# trs80_m2.net
KiCad netlist of a schematic drawn in EAGLE
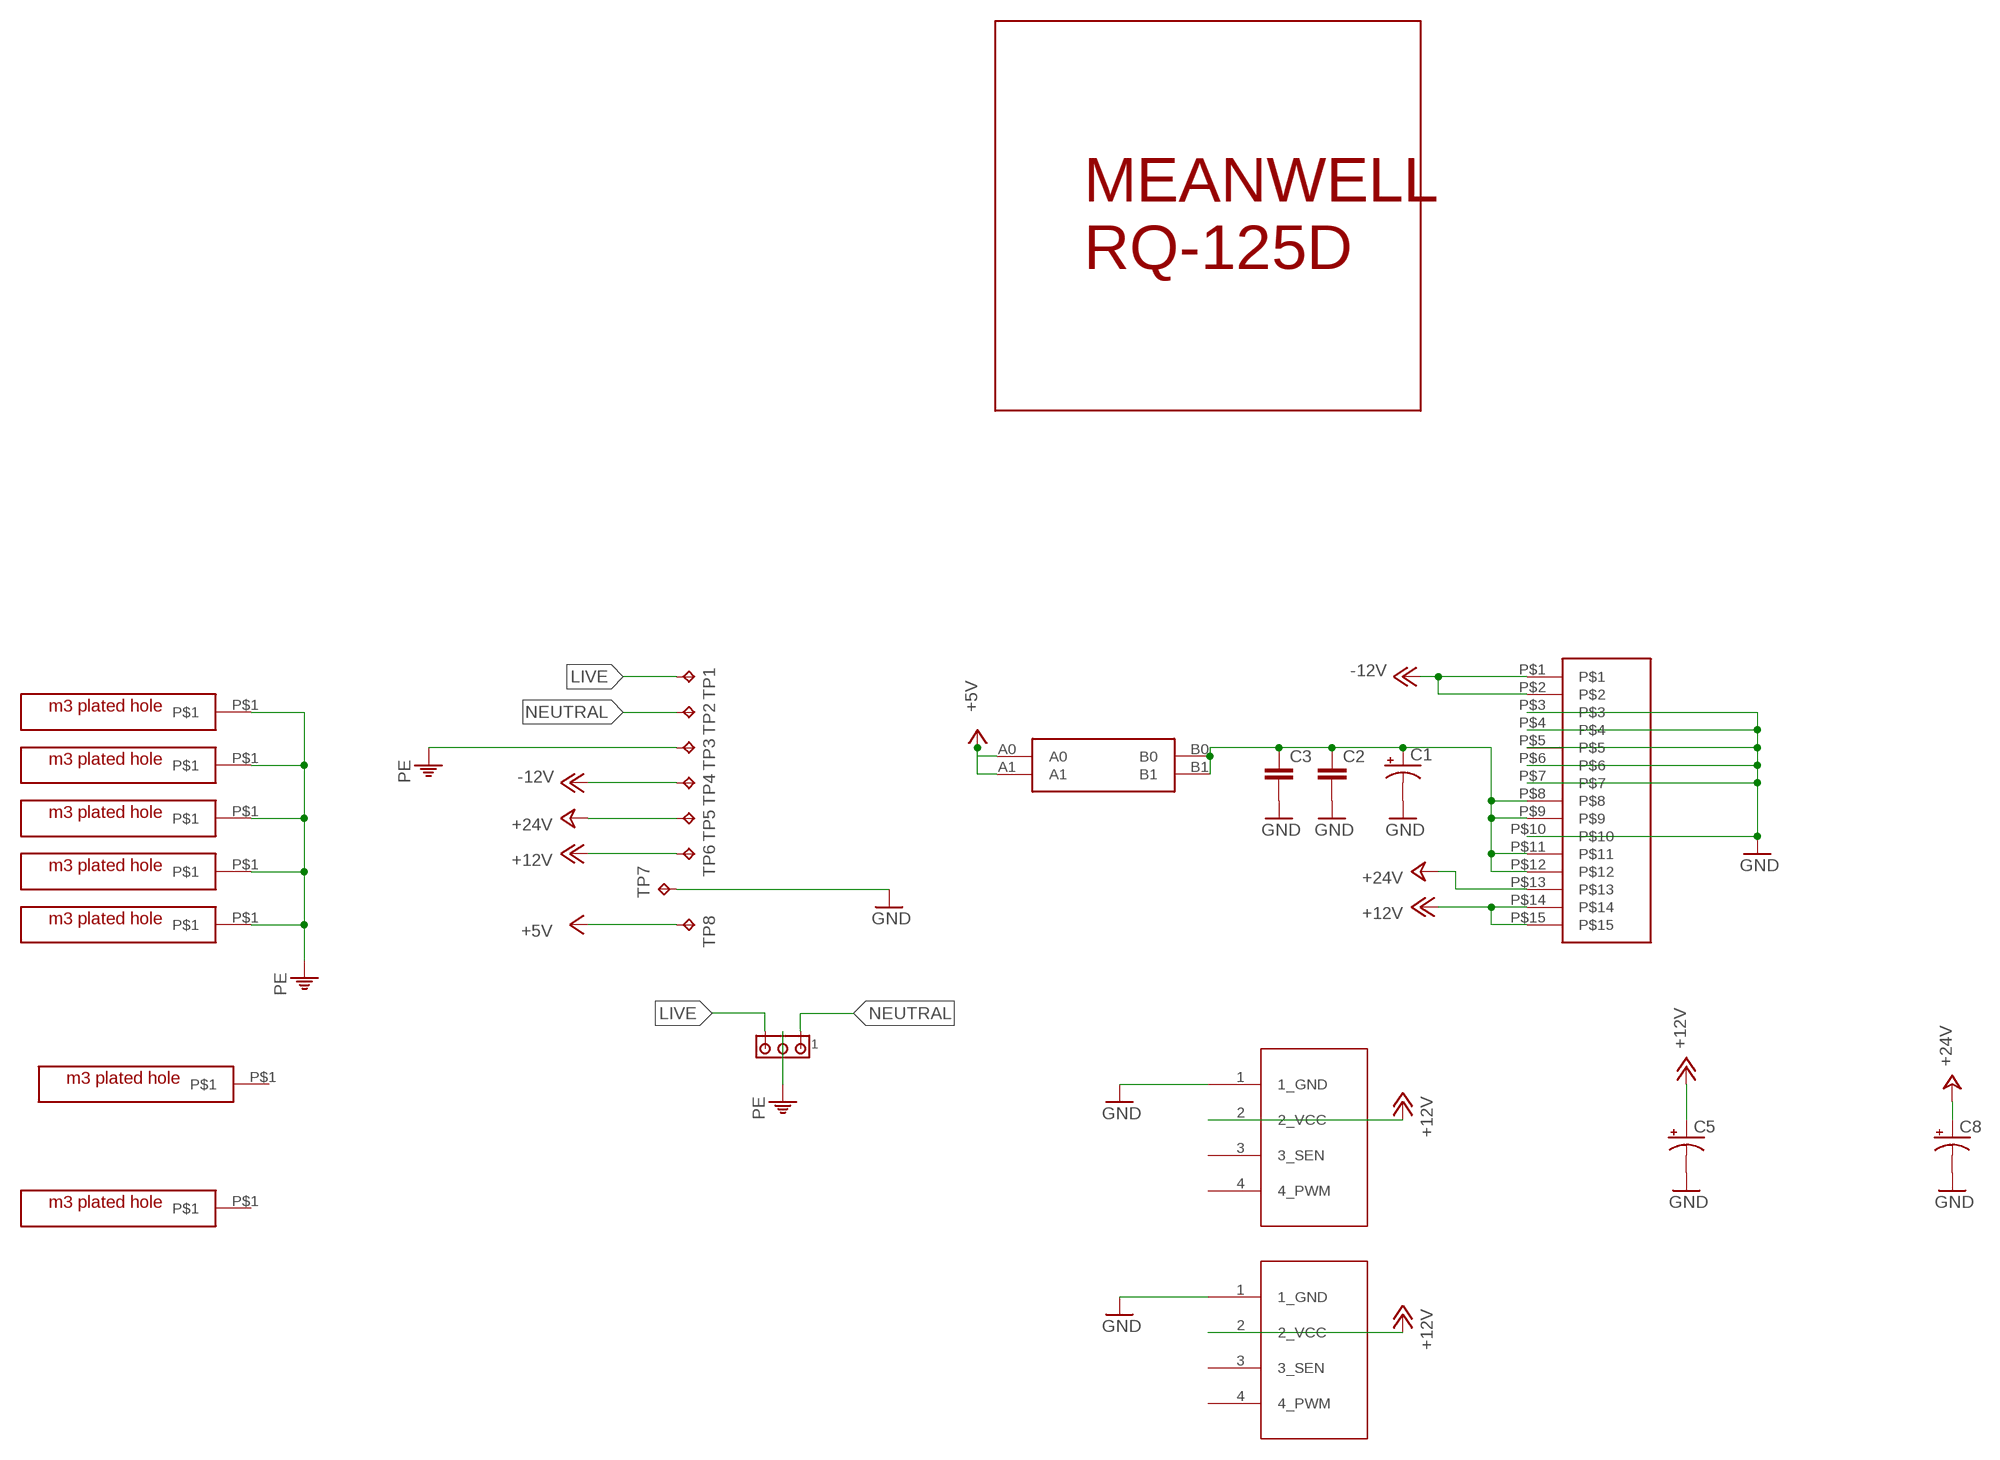
[diagram p0: schematic, sheet 1]

(export (version "E")
  (design (tool "Eeschema 10.0.6"))
  (components
    (comp (ref "C1")
      (value "CPOL-USE3.5-8")
      (footprint "eagle-import:E3,5-8")
      (libsource (lib "eagle-import") (part "CPOL-USE3.5-8"))
    )
    (comp (ref "C2")
      (value "C5/2.5")
      (footprint "eagle-import:C5B2.5")
      (libsource (lib "eagle-import") (part "C5/2.5"))
    )
    (comp (ref "C3")
      (value "C5/2.5")
      (footprint "eagle-import:C5B2.5")
      (libsource (lib "eagle-import") (part "C5/2.5"))
    )
    (comp (ref "C5")
      (value "CPOL-USE3.5-8")
      (footprint "eagle-import:E3,5-8")
      (libsource (lib "eagle-import") (part "CPOL-USE3.5-8"))
    )
    (comp (ref "C8")
      (value "CPOL-USE3.5-8")
      (footprint "eagle-import:E3,5-8")
      (libsource (lib "eagle-import") (part "CPOL-USE3.5-8"))
    )
    (comp (ref "J1")
      (value "350760-4")
      (footprint "eagle-import:350760-4")
      (libsource (lib "eagle-import") (part "350760-4"))
    )
    (comp (ref "JP1")
      (value "4PIN_FAN")
      (footprint "eagle-import:1X04")
      (libsource (lib "eagle-import") (part "4PIN_FAN"))
    )
    (comp (ref "JP4")
      (value "4PIN_FAN")
      (footprint "eagle-import:1X04")
      (libsource (lib "eagle-import") (part "4PIN_FAN"))
    )
    (comp (ref "TP1")
      (value "TPPAD1-20Y")
      (footprint "eagle-import:P1-20Y")
      (libsource (lib "eagle-import") (part "TPPAD1-20Y"))
    )
    (comp (ref "TP2")
      (value "TPPAD1-20Y")
      (footprint "eagle-import:P1-20Y")
      (libsource (lib "eagle-import") (part "TPPAD1-20Y"))
    )
    (comp (ref "TP3")
      (value "TPPAD1-20Y")
      (footprint "eagle-import:P1-20Y")
      (libsource (lib "eagle-import") (part "TPPAD1-20Y"))
    )
    (comp (ref "TP4")
      (value "TPPAD1-20Y")
      (footprint "eagle-import:P1-20Y")
      (libsource (lib "eagle-import") (part "TPPAD1-20Y"))
    )
    (comp (ref "TP5")
      (value "TPPAD1-20Y")
      (footprint "eagle-import:P1-20Y")
      (libsource (lib "eagle-import") (part "TPPAD1-20Y"))
    )
    (comp (ref "TP6")
      (value "TPPAD1-20Y")
      (footprint "eagle-import:P1-20Y")
      (libsource (lib "eagle-import") (part "TPPAD1-20Y"))
    )
    (comp (ref "TP7")
      (value "TPPAD1-20Y")
      (footprint "eagle-import:P1-20Y")
      (libsource (lib "eagle-import") (part "TPPAD1-20Y"))
    )
    (comp (ref "TP8")
      (value "TPPAD1-20Y")
      (footprint "eagle-import:P1-20Y")
      (libsource (lib "eagle-import") (part "TPPAD1-20Y"))
    )
    (comp (ref "U$2")
      (value "MEANWELL_RQ_125D")
      (footprint "eagle-import:MEANWELL_RQ125D")
      (libsource (lib "eagle-import") (part "MEANWELL_RQ_125D"))
    )
    (comp (ref "U$3")
      (value "TE_3X5")
      (footprint "eagle-import:TRS80M2_3X5")
      (libsource (lib "eagle-import") (part "TE_3X5"))
    )
    (comp (ref "U$4")
      (value "M3_HOLE_PLATED")
      (footprint "eagle-import:M3_HOLE_PLATED")
      (libsource (lib "eagle-import") (part "M3_HOLE_PLATED"))
    )
    (comp (ref "U$5")
      (value "M3_HOLE_PLATED")
      (footprint "eagle-import:M3_HOLE_PLATED")
      (libsource (lib "eagle-import") (part "M3_HOLE_PLATED"))
    )
    (comp (ref "U$6")
      (value "M3_HOLE_PLATED")
      (footprint "eagle-import:M3_HOLE_PLATED")
      (libsource (lib "eagle-import") (part "M3_HOLE_PLATED"))
    )
    (comp (ref "U$7")
      (value "M3_HOLE_PLATED")
      (footprint "eagle-import:M3_HOLE_PLATED")
      (libsource (lib "eagle-import") (part "M3_HOLE_PLATED"))
    )
    (comp (ref "U$8")
      (value "M3_HOLE_PLATED")
      (footprint "eagle-import:M3_HOLE_PLATED")
      (libsource (lib "eagle-import") (part "M3_HOLE_PLATED"))
    )
    (comp (ref "U$9")
      (value "CAR_FUSE_HOLDER3IN1")
      (footprint "eagle-import:FUSE_HOLDER_3IN1")
      (libsource (lib "eagle-import") (part "CAR_FUSE_HOLDER3IN1"))
    )
    (comp (ref "U$10")
      (value "M3_HOLE_PLATED")
      (footprint "eagle-import:M3_HOLE_PLATED")
      (libsource (lib "eagle-import") (part "M3_HOLE_PLATED"))
    )
    (comp (ref "U$11")
      (value "M3_HOLE_PLATED")
      (footprint "eagle-import:M3_HOLE_PLATED")
      (libsource (lib "eagle-import") (part "M3_HOLE_PLATED"))
    )
  )
  (nets
    (net (code "1") (name "+5V") (class "Default")
      (node (ref "TP8") (pin "TP") (pinfunction "TP_TP") (pintype "input"))
      (node (ref "U$9") (pin "A0") (pinfunction "A0_A0") (pintype "bidirectional"))
      (node (ref "U$9") (pin "A1") (pinfunction "A1_A1") (pintype "bidirectional"))
    )
    (net (code "2") (name "+12V") (class "Default")
      (node (ref "C5") (pin "+") (pinfunction "+_+") (pintype "passive"))
      (node (ref "JP1") (pin "2") (pinfunction "2_VCC_2") (pintype "passive"))
      (node (ref "JP4") (pin "2") (pinfunction "2_VCC_2") (pintype "passive"))
      (node (ref "TP6") (pin "TP") (pinfunction "TP_TP") (pintype "input"))
      (node (ref "U$3") (pin "P$14") (pinfunction "P$14_P$14") (pintype "bidirectional"))
      (node (ref "U$3") (pin "P$15") (pinfunction "P$15_P$15") (pintype "bidirectional"))
    )
    (net (code "3") (name "+24V") (class "Default")
      (node (ref "C8") (pin "+") (pinfunction "+_+") (pintype "passive"))
      (node (ref "TP5") (pin "TP") (pinfunction "TP_TP") (pintype "input"))
      (node (ref "U$3") (pin "P$13") (pinfunction "P$13_P$13") (pintype "bidirectional"))
    )
    (net (code "4") (name "-12V") (class "Default")
      (node (ref "TP4") (pin "TP") (pinfunction "TP_TP") (pintype "input"))
      (node (ref "U$3") (pin "P$1") (pinfunction "P$1_P$1") (pintype "bidirectional"))
      (node (ref "U$3") (pin "P$2") (pinfunction "P$2_P$2") (pintype "bidirectional"))
    )
    (net (code "5") (name "GND") (class "Default")
      (node (ref "C1") (pin "-") (pinfunction "-_-") (pintype "passive"))
      (node (ref "C2") (pin "2") (pinfunction "2_2") (pintype "passive"))
      (node (ref "C3") (pin "2") (pinfunction "2_2") (pintype "passive"))
      (node (ref "C5") (pin "-") (pinfunction "-_-") (pintype "passive"))
      (node (ref "C8") (pin "-") (pinfunction "-_-") (pintype "passive"))
      (node (ref "JP1") (pin "1") (pinfunction "1_GND_1") (pintype "passive"))
      (node (ref "JP4") (pin "1") (pinfunction "1_GND_1") (pintype "passive"))
      (node (ref "TP7") (pin "TP") (pinfunction "TP_TP") (pintype "input"))
      (node (ref "U$3") (pin "P$10") (pinfunction "P$10_P$10") (pintype "bidirectional"))
      (node (ref "U$3") (pin "P$3") (pinfunction "P$3_P$3") (pintype "bidirectional"))
      (node (ref "U$3") (pin "P$4") (pinfunction "P$4_P$4") (pintype "bidirectional"))
      (node (ref "U$3") (pin "P$5") (pinfunction "P$5_P$5") (pintype "bidirectional"))
      (node (ref "U$3") (pin "P$6") (pinfunction "P$6_P$6") (pintype "bidirectional"))
      (node (ref "U$3") (pin "P$7") (pinfunction "P$7_P$7") (pintype "bidirectional"))
    )
    (net (code "6") (name "LIVE") (class "Default")
      (node (ref "J1") (pin "3") (pinfunction "3_3") (pintype "passive"))
      (node (ref "TP1") (pin "TP") (pinfunction "TP_TP") (pintype "input"))
    )
    (net (code "7") (name "NEUTRAL") (class "Default")
      (node (ref "J1") (pin "1") (pinfunction "1_1") (pintype "passive"))
      (node (ref "TP2") (pin "TP") (pinfunction "TP_TP") (pintype "input"))
    )
    (net (code "8") (name "Net-(C1-Pad+)") (class "Default")
      (node (ref "C1") (pin "+") (pinfunction "+_+") (pintype "passive"))
      (node (ref "C2") (pin "1") (pinfunction "1_1") (pintype "passive"))
      (node (ref "C3") (pin "1") (pinfunction "1_1") (pintype "passive"))
      (node (ref "U$3") (pin "P$11") (pinfunction "P$11_P$11") (pintype "bidirectional"))
      (node (ref "U$3") (pin "P$12") (pinfunction "P$12_P$12") (pintype "bidirectional"))
      (node (ref "U$3") (pin "P$8") (pinfunction "P$8_P$8") (pintype "bidirectional"))
      (node (ref "U$3") (pin "P$9") (pinfunction "P$9_P$9") (pintype "bidirectional"))
      (node (ref "U$9") (pin "B0") (pinfunction "B0_B0") (pintype "bidirectional"))
      (node (ref "U$9") (pin "B1") (pinfunction "B1_B1") (pintype "bidirectional"))
    )
    (net (code "9") (name "PE") (class "Default")
      (node (ref "J1") (pin "2") (pinfunction "2_2") (pintype "passive"))
      (node (ref "TP3") (pin "TP") (pinfunction "TP_TP") (pintype "input"))
      (node (ref "U$4") (pin "P$1") (pinfunction "P$1_P$1") (pintype "bidirectional"))
      (node (ref "U$5") (pin "P$1") (pinfunction "P$1_P$1") (pintype "bidirectional"))
      (node (ref "U$6") (pin "P$1") (pinfunction "P$1_P$1") (pintype "bidirectional"))
      (node (ref "U$7") (pin "P$1") (pinfunction "P$1_P$1") (pintype "bidirectional"))
      (node (ref "U$8") (pin "P$1") (pinfunction "P$1_P$1") (pintype "bidirectional"))
    )
    (net (code "10") (name "unconnected-(JP1-3_SEN-Pad3)") (class "Default")
      (node (ref "JP1") (pin "3") (pinfunction "3_SEN_3") (pintype "passive"))
    )
    (net (code "11") (name "unconnected-(JP1-4_PWM-Pad4)") (class "Default")
      (node (ref "JP1") (pin "4") (pinfunction "4_PWM_4") (pintype "passive"))
    )
    (net (code "12") (name "unconnected-(JP4-3_SEN-Pad3)") (class "Default")
      (node (ref "JP4") (pin "3") (pinfunction "3_SEN_3") (pintype "passive"))
    )
    (net (code "13") (name "unconnected-(JP4-4_PWM-Pad4)") (class "Default")
      (node (ref "JP4") (pin "4") (pinfunction "4_PWM_4") (pintype "passive"))
    )
    (net (code "14") (name "unconnected-(U$10-PadP$1)") (class "Default")
      (node (ref "U$10") (pin "P$1") (pinfunction "P$1_P$1") (pintype "bidirectional"))
    )
    (net (code "15") (name "unconnected-(U$11-PadP$1)") (class "Default")
      (node (ref "U$11") (pin "P$1") (pinfunction "P$1_P$1") (pintype "bidirectional"))
    )
  )
)
